# QFN48_ESP32-D0WD-V3_EXP_pac.net
KiCad netlist of a schematic drawn in EAGLE
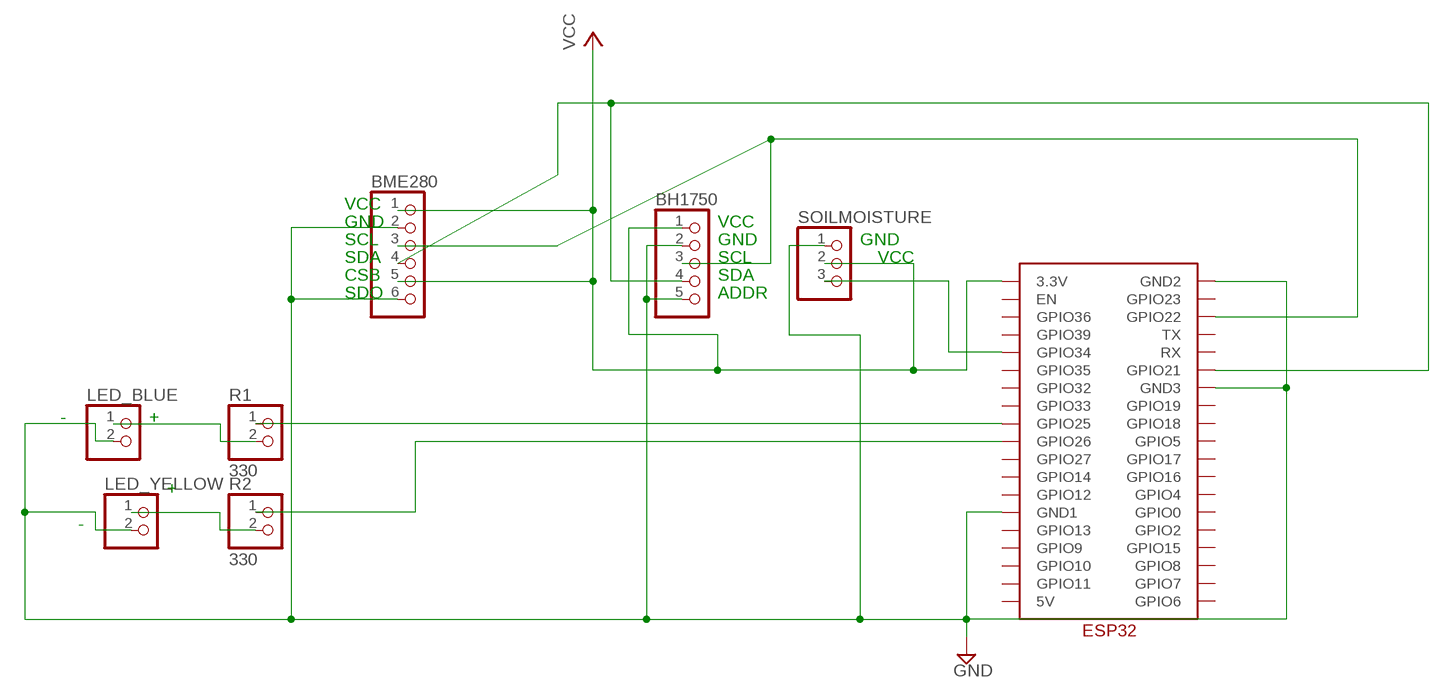
[diagram p0: schematic, sheet 1]

(export (version "E")
  (design (tool "Eeschema 10.0.6"))
  (components
    (comp (ref "BH1750")
      (value "PINHD-1X5/90")
      (footprint "eagle-import:1X05_90")
      (libsource (lib "eagle-import") (part "PINHD-1X5/90"))
    )
    (comp (ref "BME280")
      (value "PINHD-1X6/90")
      (footprint "eagle-import:1X06_90")
      (libsource (lib "eagle-import") (part "PINHD-1X6/90"))
    )
    (comp (ref "LED_BLUE")
      (value "PINHD-1X2/90")
      (footprint "eagle-import:1X02_90")
      (libsource (lib "eagle-import") (part "PINHD-1X2/90"))
    )
    (comp (ref "LED_YELLOW")
      (value "PINHD-1X2/90")
      (footprint "eagle-import:1X02_90")
      (libsource (lib "eagle-import") (part "PINHD-1X2/90"))
    )
    (comp (ref "R1")
      (value "330")
      (footprint "eagle-import:1X02_90")
      (libsource (lib "eagle-import") (part "PINHD-1X2/90"))
    )
    (comp (ref "R2")
      (value "330")
      (footprint "eagle-import:1X02_90")
      (libsource (lib "eagle-import") (part "PINHD-1X2/90"))
    )
    (comp (ref "SOILMOISTURE")
      (value "PINHD-1X3/90")
      (footprint "eagle-import:1X03_90")
      (libsource (lib "eagle-import") (part "PINHD-1X3/90"))
    )
    (comp (ref "U$1")
      (value "ESP32")
      (footprint "eagle-import:ESP32")
      (libsource (lib "eagle-import") (part "ESP32"))
    )
  )
  (nets
    (net (code "1") (name "GND") (class "Default")
      (node (ref "BH1750") (pin "2") (pinfunction "2_2") (pintype "passive"))
      (node (ref "BH1750") (pin "5") (pinfunction "5_5") (pintype "passive"))
      (node (ref "BME280") (pin "2") (pinfunction "2_2") (pintype "passive"))
      (node (ref "BME280") (pin "6") (pinfunction "6_6") (pintype "passive"))
      (node (ref "LED_BLUE") (pin "2") (pinfunction "2_2") (pintype "passive"))
      (node (ref "LED_YELLOW") (pin "2") (pinfunction "2_2") (pintype "passive"))
      (node (ref "SOILMOISTURE") (pin "1") (pinfunction "1_1") (pintype "passive"))
      (node (ref "U$1") (pin "GND1") (pinfunction "GND1_GND1") (pintype "bidirectional"))
      (node (ref "U$1") (pin "GND2") (pinfunction "GND2_GND2") (pintype "bidirectional"))
      (node (ref "U$1") (pin "GND3") (pinfunction "GND3_GND3") (pintype "bidirectional"))
    )
    (net (code "2") (name "Net-(BH1750-Pad3)") (class "Default")
      (node (ref "BH1750") (pin "3") (pinfunction "3_3") (pintype "passive"))
      (node (ref "BME280") (pin "3") (pinfunction "3_3") (pintype "passive"))
      (node (ref "U$1") (pin "GPIO22") (pinfunction "GPIO22_GPIO22") (pintype "bidirectional"))
    )
    (net (code "3") (name "Net-(BH1750-Pad4)") (class "Default")
      (node (ref "BH1750") (pin "4") (pinfunction "4_4") (pintype "passive"))
      (node (ref "BME280") (pin "4") (pinfunction "4_4") (pintype "passive"))
      (node (ref "U$1") (pin "GPIO21") (pinfunction "GPIO21_GPIO21") (pintype "bidirectional"))
    )
    (net (code "4") (name "Net-(LED_BLUE-Pad1)") (class "Default")
      (node (ref "LED_BLUE") (pin "1") (pinfunction "1_1") (pintype "passive"))
      (node (ref "R1") (pin "2") (pinfunction "2_2") (pintype "passive"))
    )
    (net (code "5") (name "Net-(LED_YELLOW-Pad1)") (class "Default")
      (node (ref "LED_YELLOW") (pin "1") (pinfunction "1_1") (pintype "passive"))
      (node (ref "R2") (pin "2") (pinfunction "2_2") (pintype "passive"))
    )
    (net (code "6") (name "Net-(R1-Pad1)") (class "Default")
      (node (ref "R1") (pin "1") (pinfunction "1_1") (pintype "passive"))
      (node (ref "U$1") (pin "GPIO25") (pinfunction "GPIO25_GPIO25") (pintype "bidirectional"))
    )
    (net (code "7") (name "Net-(R2-Pad1)") (class "Default")
      (node (ref "R2") (pin "1") (pinfunction "1_1") (pintype "passive"))
      (node (ref "U$1") (pin "GPIO26") (pinfunction "GPIO26_GPIO26") (pintype "bidirectional"))
    )
    (net (code "8") (name "Net-(SOILMOISTURE-Pad3)") (class "Default")
      (node (ref "SOILMOISTURE") (pin "3") (pinfunction "3_3") (pintype "passive"))
      (node (ref "U$1") (pin "GPIO34") (pinfunction "GPIO34_GPIO34") (pintype "bidirectional"))
    )
    (net (code "9") (name "VCC") (class "Default")
      (node (ref "BH1750") (pin "1") (pinfunction "1_1") (pintype "passive"))
      (node (ref "BME280") (pin "1") (pinfunction "1_1") (pintype "passive"))
      (node (ref "BME280") (pin "5") (pinfunction "5_5") (pintype "passive"))
      (node (ref "SOILMOISTURE") (pin "2") (pinfunction "2_2") (pintype "passive"))
      (node (ref "U$1") (pin "3.3V") (pinfunction "3.3V_3.3V") (pintype "bidirectional"))
    )
    (net (code "10") (name "unconnected-(U$1-Pad5V)") (class "Default")
      (node (ref "U$1") (pin "5V") (pinfunction "5V_5V") (pintype "bidirectional"))
    )
    (net (code "11") (name "unconnected-(U$1-PadEN)") (class "Default")
      (node (ref "U$1") (pin "EN") (pinfunction "EN_EN") (pintype "bidirectional"))
    )
    (net (code "12") (name "unconnected-(U$1-PadGPIO0)") (class "Default")
      (node (ref "U$1") (pin "GPIO0") (pinfunction "GPIO0_GPIO0") (pintype "bidirectional"))
    )
    (net (code "13") (name "unconnected-(U$1-PadGPIO2)") (class "Default")
      (node (ref "U$1") (pin "GPIO2") (pinfunction "GPIO2_GPIO2") (pintype "bidirectional"))
    )
    (net (code "14") (name "unconnected-(U$1-PadGPIO4)") (class "Default")
      (node (ref "U$1") (pin "GPIO4") (pinfunction "GPIO4_GPIO4") (pintype "bidirectional"))
    )
    (net (code "15") (name "unconnected-(U$1-PadGPIO5)") (class "Default")
      (node (ref "U$1") (pin "GPIO5") (pinfunction "GPIO5_GPIO5") (pintype "bidirectional"))
    )
    (net (code "16") (name "unconnected-(U$1-PadGPIO6)") (class "Default")
      (node (ref "U$1") (pin "GPIO6") (pinfunction "GPIO6_GPIO6") (pintype "bidirectional"))
    )
    (net (code "17") (name "unconnected-(U$1-PadGPIO7)") (class "Default")
      (node (ref "U$1") (pin "GPIO7") (pinfunction "GPIO7_GPIO7") (pintype "bidirectional"))
    )
    (net (code "18") (name "unconnected-(U$1-PadGPIO8)") (class "Default")
      (node (ref "U$1") (pin "GPIO8") (pinfunction "GPIO8_GPIO8") (pintype "bidirectional"))
    )
    (net (code "19") (name "unconnected-(U$1-PadGPIO9)") (class "Default")
      (node (ref "U$1") (pin "GPIO9") (pinfunction "GPIO9_GPIO9") (pintype "bidirectional"))
    )
    (net (code "20") (name "unconnected-(U$1-PadGPIO10)") (class "Default")
      (node (ref "U$1") (pin "GPIO10") (pinfunction "GPIO10_GPIO10") (pintype "bidirectional"))
    )
    (net (code "21") (name "unconnected-(U$1-PadGPIO11)") (class "Default")
      (node (ref "U$1") (pin "GPIO11") (pinfunction "GPIO11_GPIO11") (pintype "bidirectional"))
    )
    (net (code "22") (name "unconnected-(U$1-PadGPIO12)") (class "Default")
      (node (ref "U$1") (pin "GPIO12") (pinfunction "GPIO12_GPIO12") (pintype "bidirectional"))
    )
    (net (code "23") (name "unconnected-(U$1-PadGPIO13)") (class "Default")
      (node (ref "U$1") (pin "GPIO13") (pinfunction "GPIO13_GPIO13") (pintype "bidirectional"))
    )
    (net (code "24") (name "unconnected-(U$1-PadGPIO14)") (class "Default")
      (node (ref "U$1") (pin "GPIO14") (pinfunction "GPIO14_GPIO14") (pintype "bidirectional"))
    )
    (net (code "25") (name "unconnected-(U$1-PadGPIO15)") (class "Default")
      (node (ref "U$1") (pin "GPIO15") (pinfunction "GPIO15_GPIO15") (pintype "bidirectional"))
    )
    (net (code "26") (name "unconnected-(U$1-PadGPIO16)") (class "Default")
      (node (ref "U$1") (pin "GPIO16") (pinfunction "GPIO16_GPIO16") (pintype "bidirectional"))
    )
    (net (code "27") (name "unconnected-(U$1-PadGPIO17)") (class "Default")
      (node (ref "U$1") (pin "GPIO17") (pinfunction "GPIO17_GPIO17") (pintype "bidirectional"))
    )
    (net (code "28") (name "unconnected-(U$1-PadGPIO18)") (class "Default")
      (node (ref "U$1") (pin "GPIO18") (pinfunction "GPIO18_GPIO18") (pintype "bidirectional"))
    )
    (net (code "29") (name "unconnected-(U$1-PadGPIO19)") (class "Default")
      (node (ref "U$1") (pin "GPIO19") (pinfunction "GPIO19_GPIO19") (pintype "bidirectional"))
    )
    (net (code "30") (name "unconnected-(U$1-PadGPIO23)") (class "Default")
      (node (ref "U$1") (pin "GPIO23") (pinfunction "GPIO23_GPIO23") (pintype "bidirectional"))
    )
    (net (code "31") (name "unconnected-(U$1-PadGPIO27)") (class "Default")
      (node (ref "U$1") (pin "GPIO27") (pinfunction "GPIO27_GPIO27") (pintype "bidirectional"))
    )
    (net (code "32") (name "unconnected-(U$1-PadGPIO32)") (class "Default")
      (node (ref "U$1") (pin "GPIO32") (pinfunction "GPIO32_GPIO32") (pintype "bidirectional"))
    )
    (net (code "33") (name "unconnected-(U$1-PadGPIO33)") (class "Default")
      (node (ref "U$1") (pin "GPIO33") (pinfunction "GPIO33_GPIO33") (pintype "bidirectional"))
    )
    (net (code "34") (name "unconnected-(U$1-PadGPIO35)") (class "Default")
      (node (ref "U$1") (pin "GPIO35") (pinfunction "GPIO35_GPIO35") (pintype "bidirectional"))
    )
    (net (code "35") (name "unconnected-(U$1-PadGPIO36)") (class "Default")
      (node (ref "U$1") (pin "GPIO36") (pinfunction "GPIO36_GPIO36") (pintype "bidirectional"))
    )
    (net (code "36") (name "unconnected-(U$1-PadGPIO39)") (class "Default")
      (node (ref "U$1") (pin "GPIO39") (pinfunction "GPIO39_GPIO39") (pintype "bidirectional"))
    )
    (net (code "37") (name "unconnected-(U$1-PadRX)") (class "Default")
      (node (ref "U$1") (pin "RX") (pinfunction "RX_RX") (pintype "bidirectional"))
    )
    (net (code "38") (name "unconnected-(U$1-PadTX)") (class "Default")
      (node (ref "U$1") (pin "TX") (pinfunction "TX_TX") (pintype "bidirectional"))
    )
  )
)
